# LB-char-coilRectifier.net
KiCad netlist of a schematic drawn in Altium Designer
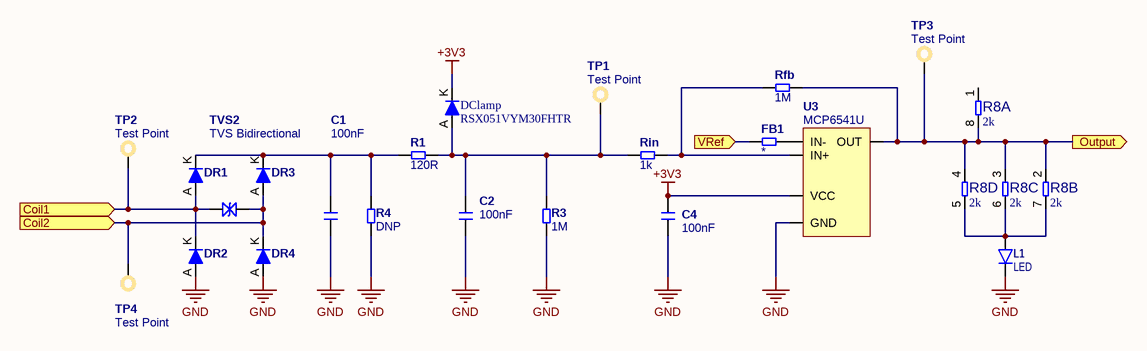
[diagram p0: LB-char-coilRectifier.SchDoc]

(export (version "E")
  (design (tool "Eeschema 10.0.6"))
  (components
    (comp (ref "C1")
      (value "100nF")
      (footprint "C0603_N")
      (description "Capacitor MLCC")
      (fields
        (field (name "MANUFACTURER") "Yageo")
        (field (name "MANUFACTURER PART NUMBER") "CC0603KRX7R9BB104")
      )
      (libsource (lib "wes") (part "Capacitor"))
    )
    (comp (ref "C2")
      (value "100nF")
      (footprint "C0603_N")
      (description "Capacitor MLCC")
      (fields
        (field (name "MANUFACTURER") "Yageo")
        (field (name "MANUFACTURER PART NUMBER") "CC0603KRX7R9BB104")
      )
      (libsource (lib "wes") (part "Capacitor"))
    )
    (comp (ref "C4")
      (value "100nF")
      (footprint "C0603_N")
      (description "Capacitor MLCC")
      (fields
        (field (name "MANUFACTURER") "Yageo")
        (field (name "MANUFACTURER PART NUMBER") "CC0603KRX7R9BB104")
      )
      (libsource (lib "wes") (part "Capacitor"))
    )
    (comp (ref "DClamp")
      (value "RSX051VYM30FHTR")
      (footprint "SOD323F")
      (libsource (lib "wes") (part "Diode"))
    )
    (comp (ref "DR1") (value "RSX051VYM30FHTR") (footprint "SOD323F") (libsource (lib "wes") (part "Diode")))
    (comp (ref "DR2") (value "RSX051VYM30FHTR") (footprint "SOD323F") (libsource (lib "wes") (part "Diode")))
    (comp (ref "DR3") (value "RSX051VYM30FHTR") (footprint "SOD323F") (libsource (lib "wes") (part "Diode")))
    (comp (ref "DR4") (value "RSX051VYM30FHTR") (footprint "SOD323F") (libsource (lib "wes") (part "Diode")))
    (comp (ref "FB1")
      (value "FB")
      (footprint "R0603")
      (fields (field (name "ALTIUM_VALUE") "*") (field (name "PUBLISHER") "Altium Limited"))
      (libsource (lib "wes") (part "Resistor"))
    )
    (comp (ref "L1") (value "LED") (footprint "LED 0603/1608") (libsource (lib "wes") (part "LED")))
    (comp (ref "R1")
      (value "120R")
      (footprint "R0603")
      (fields (field (name "PUBLISHER") "Altium Limited"))
      (libsource (lib "wes") (part "Resistor"))
    )
    (comp (ref "R3")
      (value "1M")
      (footprint "R0603")
      (fields (field (name "PUBLISHER") "Altium Limited"))
      (libsource (lib "wes") (part "Resistor"))
    )
    (comp (ref "R4")
      (value "DNP")
      (footprint "R0603")
      (fields (field (name "PUBLISHER") "Altium Limited"))
      (libsource (lib "wes") (part "Resistor"))
    )
    (comp (ref "R8")
      (value "2k")
      (footprint "YC164")
      (fields (field (name "Comment") "; 2k"))
      (libsource (lib "wes") (part "Resistor Array - 4P"))
    )
    (comp (ref "Rfb")
      (value "1M")
      (footprint "R0603")
      (fields (field (name "PUBLISHER") "Altium Limited"))
      (libsource (lib "wes") (part "Resistor"))
    )
    (comp (ref "Rin")
      (value "1k")
      (footprint "R0603")
      (fields (field (name "PUBLISHER") "Altium Limited"))
      (libsource (lib "wes") (part "Resistor"))
    )
    (comp (ref "TP1")
      (value "Test Point")
      (footprint "Harwin S2751-46R")
      (libsource (lib "wes") (part "Test Point"))
    )
    (comp (ref "TP2")
      (value "Test Point")
      (footprint "Harwin S2751-46R")
      (libsource (lib "wes") (part "Test Point"))
    )
    (comp (ref "TP3")
      (value "Test Point")
      (footprint "Harwin S2751-46R")
      (libsource (lib "wes") (part "Test Point"))
    )
    (comp (ref "TP4")
      (value "Test Point")
      (footprint "Harwin S2751-46R")
      (libsource (lib "wes") (part "Test Point"))
    )
    (comp (ref "TVS2")
      (value "TVS Bidirectional")
      (footprint "SOD323F-Comchip Variant")
      (libsource (lib "wes") (part "TVS Bidirectional"))
    )
    (comp (ref "U3") (value "MCP6541U") (footprint "SOT23-5_N") (libsource (lib "wes") (part "MCP6541U")))
  )
  (nets
    (net (code "1") (name "+3V3") (class "Default")
      (node (ref "C4") (pin "1") (pintype "passive"))
      (node (ref "DClamp") (pin "K") (pinfunction "K_K") (pintype "passive"))
      (node (ref "U3") (pin "5") (pinfunction "VCC_5") (pintype "passive"))
    )
    (net (code "2") (name "/Coil1") (class "Default")
      (node (ref "DR1") (pin "A") (pinfunction "A_A") (pintype "passive"))
      (node (ref "DR2") (pin "K") (pinfunction "K_K") (pintype "passive"))
      (node (ref "TP2") (pin "1") (pinfunction "1_1") (pintype "passive"))
      (node (ref "TVS2") (pin "2") (pinfunction "2_2") (pintype "passive"))
    )
    (net (code "3") (name "/Coil2") (class "Default")
      (node (ref "DR3") (pin "A") (pinfunction "A_A") (pintype "passive"))
      (node (ref "DR4") (pin "K") (pinfunction "K_K") (pintype "passive"))
      (node (ref "TP4") (pin "1") (pinfunction "1_1") (pintype "passive"))
      (node (ref "TVS2") (pin "1") (pinfunction "1_1") (pintype "passive"))
    )
    (net (code "4") (name "/Output") (class "Default")
      (node (ref "R8") (pin "2") (pinfunction "2_2") (pintype "passive"))
      (node (ref "R8") (pin "3") (pinfunction "3_3") (pintype "passive"))
      (node (ref "R8") (pin "4") (pinfunction "4_4") (pintype "passive"))
      (node (ref "R8") (pin "8") (pinfunction "8_8") (pintype "passive"))
      (node (ref "Rfb") (pin "2") (pinfunction "2_2") (pintype "passive"))
      (node (ref "TP3") (pin "1") (pinfunction "1_1") (pintype "passive"))
      (node (ref "U3") (pin "4") (pinfunction "OUT_4") (pintype "passive"))
    )
    (net (code "5") (name "/VRef") (class "Default")
      (node (ref "FB1") (pin "1") (pinfunction "1_1") (pintype "passive"))
    )
    (net (code "6") (name "GND") (class "Default")
      (node (ref "C1") (pin "2") (pintype "passive"))
      (node (ref "C2") (pin "2") (pintype "passive"))
      (node (ref "C4") (pin "2") (pintype "passive"))
      (node (ref "DR2") (pin "A") (pinfunction "A_A") (pintype "passive"))
      (node (ref "DR4") (pin "A") (pinfunction "A_A") (pintype "passive"))
      (node (ref "L1") (pin "1") (pinfunction "K_1") (pintype "power_in"))
      (node (ref "R3") (pin "1") (pinfunction "1_1") (pintype "passive"))
      (node (ref "R4") (pin "1") (pinfunction "1_1") (pintype "passive"))
      (node (ref "U3") (pin "2") (pinfunction "GND_2") (pintype "passive"))
    )
    (net (code "7") (name "Net-(C1-Pad1)") (class "Default")
      (node (ref "C1") (pin "1") (pintype "passive"))
      (node (ref "DR1") (pin "K") (pinfunction "K_K") (pintype "passive"))
      (node (ref "DR3") (pin "K") (pinfunction "K_K") (pintype "passive"))
      (node (ref "R1") (pin "1") (pinfunction "1_1") (pintype "passive"))
      (node (ref "R4") (pin "2") (pinfunction "2_2") (pintype "passive"))
    )
    (net (code "8") (name "Net-(C2-Pad1)") (class "Default")
      (node (ref "C2") (pin "1") (pintype "passive"))
      (node (ref "DClamp") (pin "A") (pinfunction "A_A") (pintype "passive"))
      (node (ref "R1") (pin "2") (pinfunction "2_2") (pintype "passive"))
      (node (ref "R3") (pin "2") (pinfunction "2_2") (pintype "passive"))
      (node (ref "Rin") (pin "1") (pinfunction "1_1") (pintype "passive"))
      (node (ref "TP1") (pin "1") (pinfunction "1_1") (pintype "passive"))
    )
    (net (code "9") (name "Net-(L1-A)") (class "Default")
      (node (ref "L1") (pin "2") (pinfunction "A_2") (pintype "power_in"))
      (node (ref "R8") (pin "5") (pinfunction "5_5") (pintype "passive"))
      (node (ref "R8") (pin "6") (pinfunction "6_6") (pintype "passive"))
      (node (ref "R8") (pin "7") (pinfunction "7_7") (pintype "passive"))
    )
    (net (code "10") (name "Net-(U3-IN+)") (class "Default")
      (node (ref "Rfb") (pin "1") (pinfunction "1_1") (pintype "passive"))
      (node (ref "Rin") (pin "2") (pinfunction "2_2") (pintype "passive"))
      (node (ref "U3") (pin "1") (pinfunction "IN+_1") (pintype "passive"))
    )
    (net (code "11") (name "Net-(U3-IN-)") (class "Default")
      (node (ref "FB1") (pin "2") (pinfunction "2_2") (pintype "passive"))
      (node (ref "U3") (pin "3") (pinfunction "IN-_3") (pintype "passive"))
    )
    (net (code "12") (name "unconnected-(R8-Pad1)") (class "Default")
      (node (ref "R8") (pin "1") (pinfunction "1_1") (pintype "passive"))
    )
  )
)
